# anet-cap-z-probe.net
KiCad netlist of a schematic drawn in EAGLE
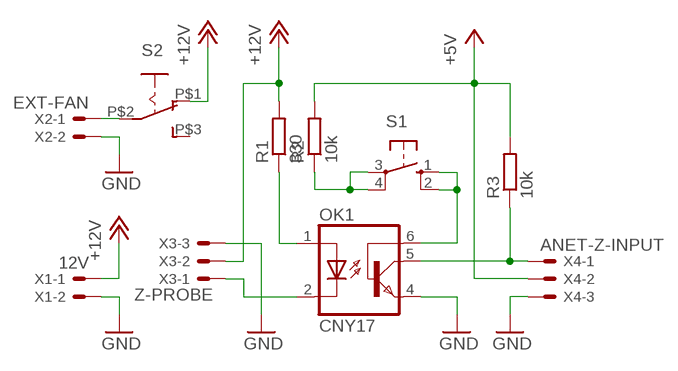
[diagram p0: schematic, sheet 1]

(export (version "E")
  (design (tool "Eeschema 10.0.6"))
  (components
    (comp (ref "OK1")
      (value "CNY17")
      (footprint "eagle-import:DIL06")
      (fields (field (name "MPN") "CNY17-1"))
      (libsource (lib "eagle-import") (part "CNY17"))
    )
    (comp (ref "R1")
      (value "330")
      (footprint "eagle-import:R0805")
      (libsource (lib "eagle-import") (part "R-EU_R0805"))
    )
    (comp (ref "R2")
      (value "10k")
      (footprint "eagle-import:R0805")
      (libsource (lib "eagle-import") (part "R-EU_R0805"))
    )
    (comp (ref "R3")
      (value "10k")
      (footprint "eagle-import:R0805")
      (libsource (lib "eagle-import") (part "R-EU_R0805"))
    )
    (comp (ref "S1")
      (value "10-XX")
      (footprint "eagle-import:B3F-10XX")
      (fields (field (name "MPN") "B3F-1000"))
      (libsource (lib "eagle-import") (part "10-XX"))
    )
    (comp (ref "S2")
      (value "EG1218THIN")
      (footprint "eagle-import:THIN")
      (libsource (lib "eagle-import") (part "EG1218THIN"))
    )
    (comp (ref "X1")
      (value "12V")
      (footprint "eagle-import:JST-XH-02-PACKAGE-LONG-PAD")
      (libsource (lib "eagle-import") (part "JST-XH-02-PIN-LONG-PAD"))
    )
    (comp (ref "X2")
      (value "EXT-FAN")
      (footprint "eagle-import:JST-XH-02-PACKAGE-LONG-PAD")
      (libsource (lib "eagle-import") (part "JST-XH-02-PIN-LONG-PAD"))
    )
    (comp (ref "X3")
      (value "Z-PROBE")
      (footprint "eagle-import:JST-XH-03-PACKAGE-LONG-PAD")
      (libsource (lib "eagle-import") (part "JST-XH-03-PIN-LONG-PAD"))
    )
    (comp (ref "X4")
      (value "ANET-Z-INPUT")
      (footprint "eagle-import:JST-XH-03-PACKAGE-LONG-PAD")
      (libsource (lib "eagle-import") (part "JST-XH-03-PIN-LONG-PAD"))
    )
  )
  (nets
    (net (code "1") (name "+5V") (class "Default")
      (node (ref "R2") (pin "2") (pinfunction "2_2") (pintype "passive"))
      (node (ref "R3") (pin "2") (pinfunction "2_2") (pintype "passive"))
      (node (ref "X4") (pin "2") (pinfunction "S_2") (pintype "passive"))
    )
    (net (code "2") (name "+12V") (class "Default")
      (node (ref "R1") (pin "2") (pinfunction "2_2") (pintype "passive"))
      (node (ref "S2") (pin "P$1") (pinfunction "O_P$1") (pintype "passive"))
      (node (ref "X1") (pin "1") (pinfunction "S_1") (pintype "passive"))
      (node (ref "X3") (pin "2") (pinfunction "S_2") (pintype "passive"))
    )
    (net (code "3") (name "GND") (class "Default")
      (node (ref "OK1") (pin "4") (pinfunction "EMI_4") (pintype "passive"))
      (node (ref "X1") (pin "2") (pinfunction "S_2") (pintype "passive"))
      (node (ref "X2") (pin "2") (pinfunction "S_2") (pintype "passive"))
      (node (ref "X3") (pin "3") (pinfunction "S_3") (pintype "passive"))
      (node (ref "X4") (pin "3") (pinfunction "S_3") (pintype "passive"))
    )
    (net (code "4") (name "Net-(OK1-A)") (class "Default")
      (node (ref "OK1") (pin "1") (pinfunction "A_1") (pintype "passive"))
      (node (ref "R1") (pin "1") (pinfunction "1_1") (pintype "passive"))
    )
    (net (code "5") (name "Net-(OK1-BAS)") (class "Default")
      (node (ref "OK1") (pin "6") (pinfunction "BAS_6") (pintype "passive"))
      (node (ref "S1") (pin "1") (pinfunction "S_1") (pintype "passive"))
      (node (ref "S1") (pin "2") (pinfunction "S1_2") (pintype "passive"))
    )
    (net (code "6") (name "Net-(OK1-C)") (class "Default")
      (node (ref "OK1") (pin "2") (pinfunction "C_2") (pintype "passive"))
      (node (ref "X3") (pin "1") (pinfunction "S_1") (pintype "passive"))
    )
    (net (code "7") (name "Net-(OK1-COL)") (class "Default")
      (node (ref "OK1") (pin "5") (pinfunction "COL_5") (pintype "passive"))
      (node (ref "R3") (pin "1") (pinfunction "1_1") (pintype "passive"))
      (node (ref "X4") (pin "1") (pinfunction "S_1") (pintype "passive"))
    )
    (net (code "8") (name "Net-(S1-P)") (class "Default")
      (node (ref "R2") (pin "1") (pinfunction "1_1") (pintype "passive"))
      (node (ref "S1") (pin "3") (pinfunction "P_3") (pintype "passive"))
      (node (ref "S1") (pin "4") (pinfunction "P1_4") (pintype "passive"))
    )
    (net (code "9") (name "Net-(S2-P)") (class "Default")
      (node (ref "S2") (pin "P$2") (pinfunction "P_P$2") (pintype "passive"))
      (node (ref "X2") (pin "1") (pinfunction "S_1") (pintype "passive"))
    )
    (net (code "10") (name "unconnected-(S2-S-PadP$3)") (class "Default")
      (node (ref "S2") (pin "P$3") (pinfunction "S_P$3") (pintype "passive"))
    )
  )
)
